# Drive.net
KiCad netlist of a schematic drawn in Altium Designer
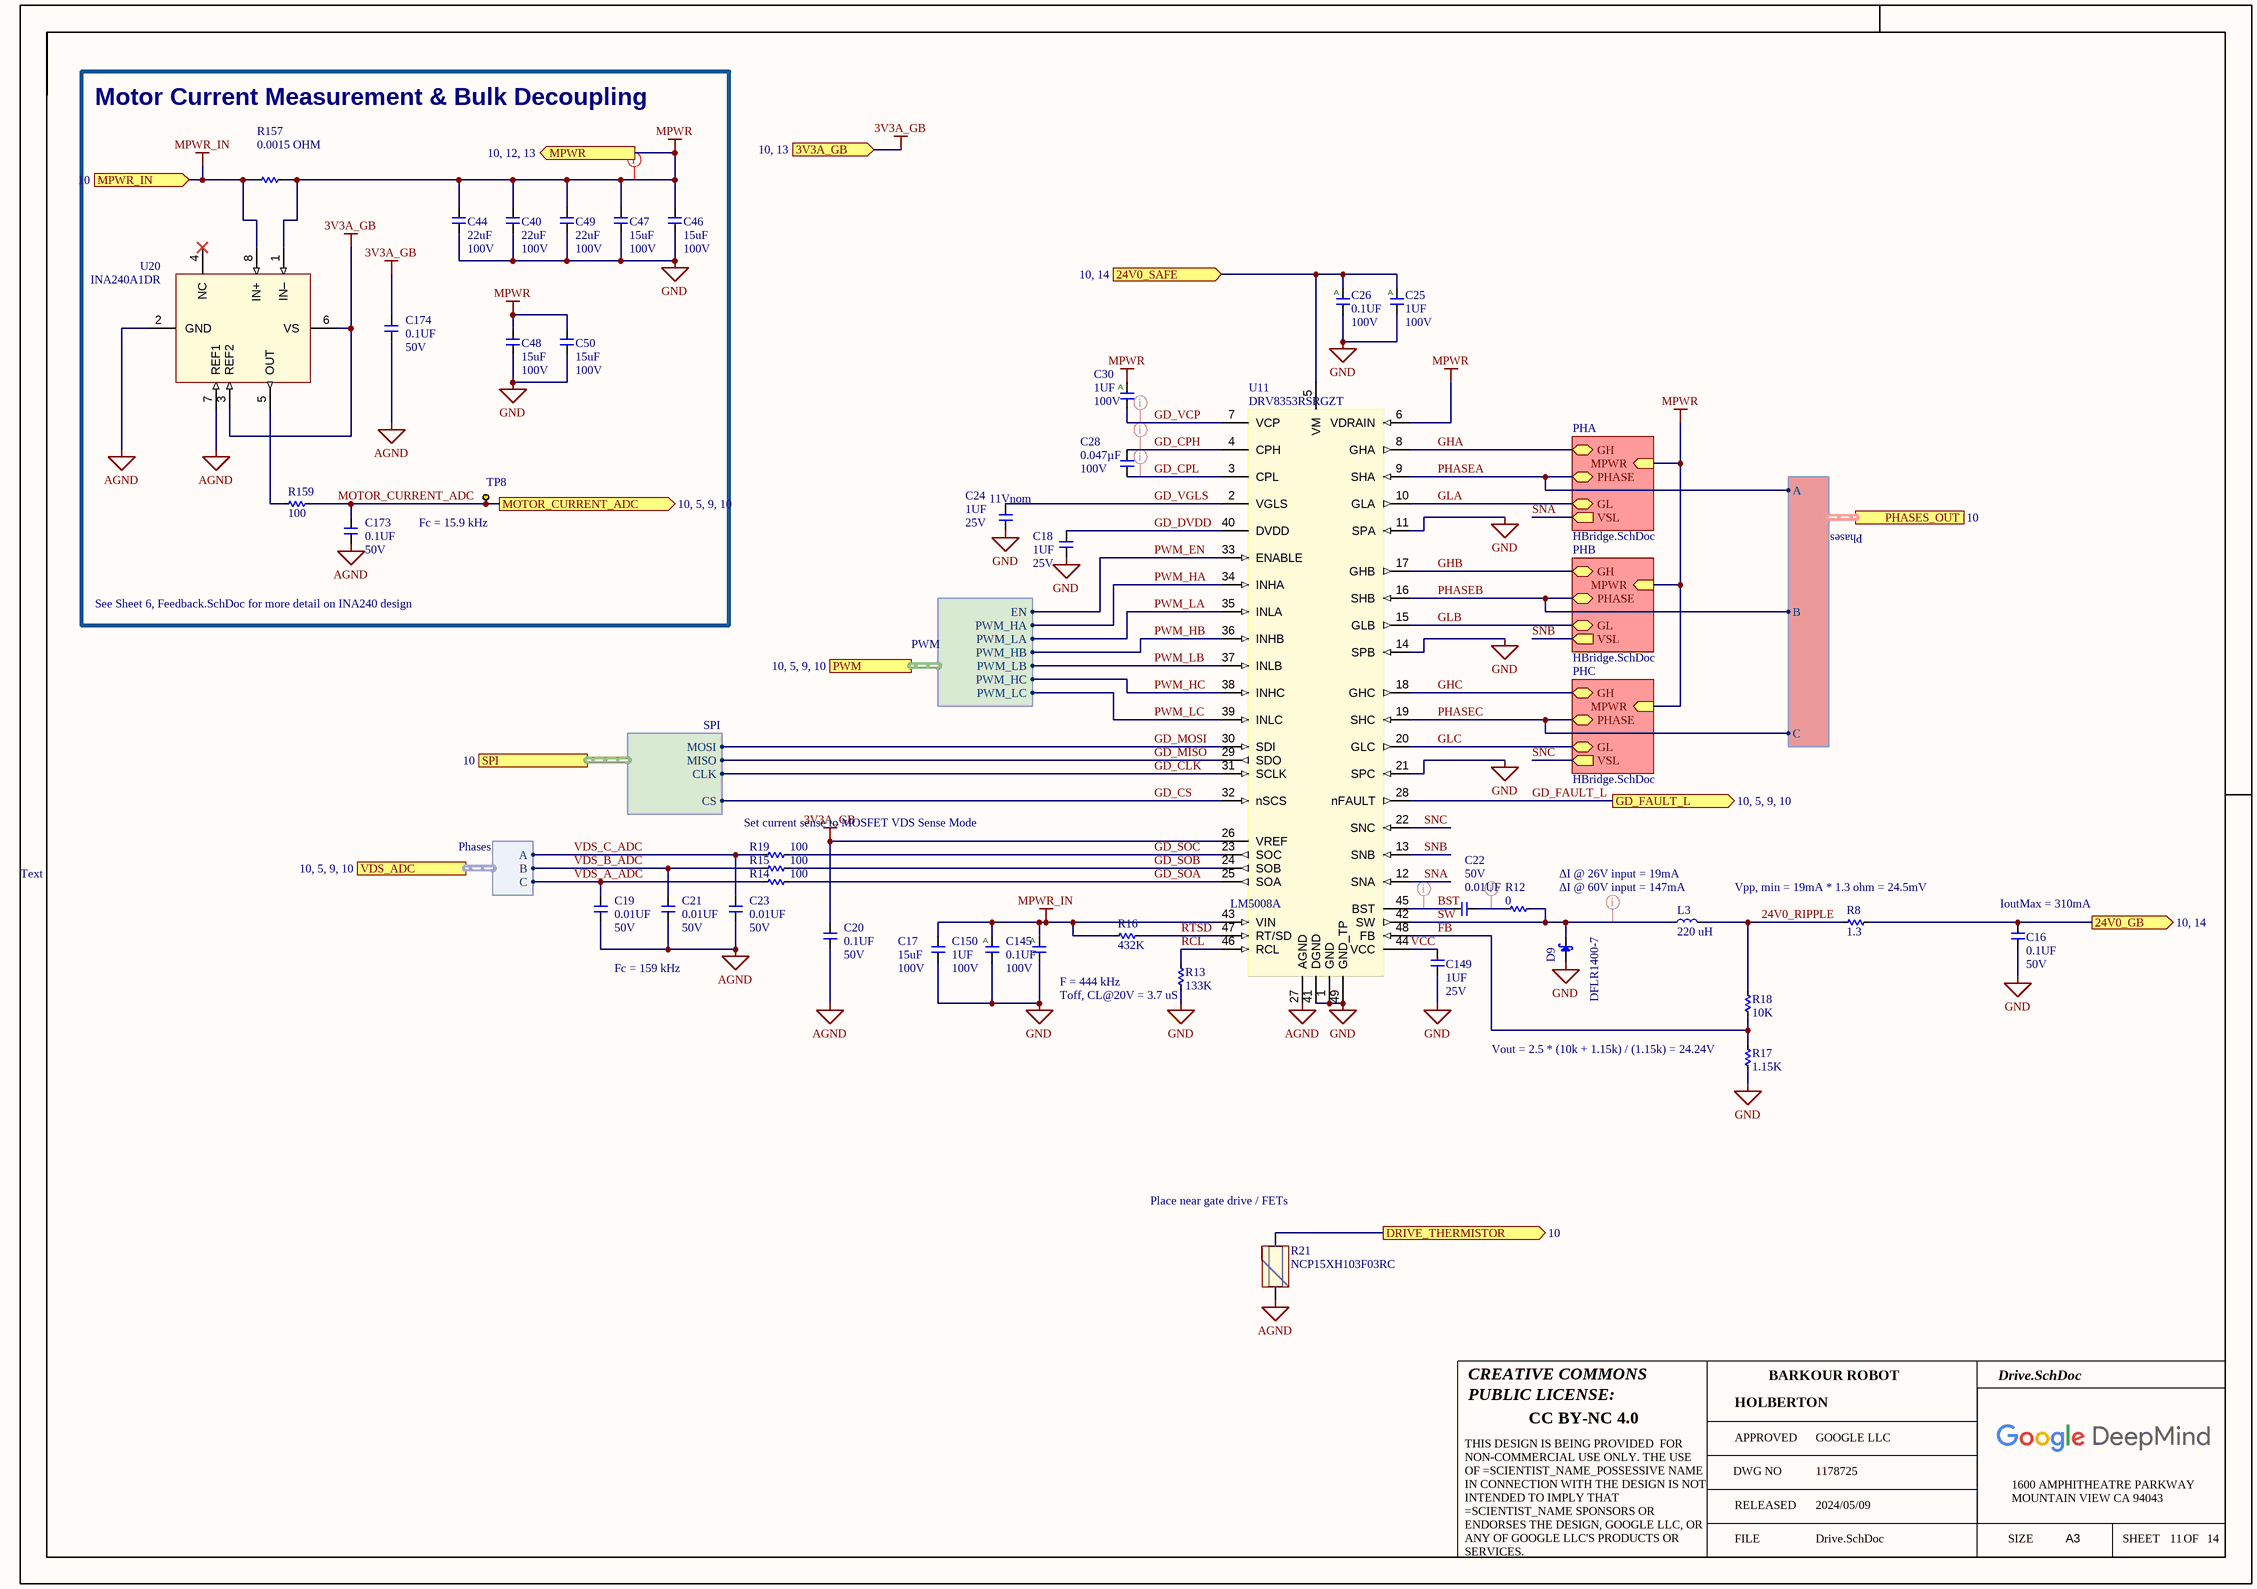
[diagram p0: Drive.SchDoc]

(export (version "E")
  (design (tool "Eeschema 10.0.6"))
  (components
    (comp (ref "C16")
      (value "0.1UF")
      (footprint "C0402")
      (description "CAP, CER, X5R, 0.1uF, 10%, 50V, 0402, 0.55mm")
      (fields
        (field (name "MFG") "YAGEO")
        (field (name "VOLTAGE") "50V")
        (field (name "Comment") "__Template_Cap")
      )
      (libsource (lib "AltiumReleaseLibDB") (part "__Template_Cap"))
    )
    (comp (ref "C17")
      (value "15uF")
      (footprint "C2220")
      (description "CAP, CER, X7S, 15uF, 100V, 20%, 2220, 2.8mm T")
      (fields
        (field (name "MFG") "TDK")
        (field (name "VOLTAGE") "100V")
        (field (name "Comment") "__Template_Cap")
      )
      (libsource (lib "AltiumReleaseLibDB") (part "__Template_Cap"))
    )
    (comp (ref "C18")
      (value "1UF")
      (footprint "C0402")
      (description "CAP, CER, X5R, 1uF, 10%, 25V, 0402")
      (fields
        (field (name "MFG") "TDK")
        (field (name "VOLTAGE") "25V")
        (field (name "Comment") "__Template_Cap")
      )
      (libsource (lib "AltiumReleaseLibDB") (part "__Template_Cap"))
    )
    (comp (ref "C19")
      (value "0.01UF")
      (footprint "C0402")
      (description "CAP, CER, X7R, 0.01uF, 50V, 20%, 0402, 0.56mm T")
      (fields
        (field (name "MFG") "KEMET")
        (field (name "VOLTAGE") "50V")
        (field (name "Comment") "__Template_Cap")
      )
      (libsource (lib "AltiumReleaseLibDB") (part "__Template_Cap"))
    )
    (comp (ref "C20")
      (value "0.1UF")
      (footprint "C0402")
      (description "CAP, CER, X5R, 0.1uF, 10%, 50V, 0402, 0.55mm")
      (fields
        (field (name "MFG") "YAGEO")
        (field (name "VOLTAGE") "50V")
        (field (name "Comment") "__Template_Cap")
      )
      (libsource (lib "AltiumReleaseLibDB") (part "__Template_Cap"))
    )
    (comp (ref "C21")
      (value "0.01UF")
      (footprint "C0402")
      (description "CAP, CER, X7R, 0.01uF, 50V, 20%, 0402, 0.56mm T")
      (fields
        (field (name "MFG") "KEMET")
        (field (name "VOLTAGE") "50V")
        (field (name "Comment") "__Template_Cap")
      )
      (libsource (lib "AltiumReleaseLibDB") (part "__Template_Cap"))
    )
    (comp (ref "C22")
      (value "0.01UF")
      (footprint "C0402")
      (description "CAP, CER, X7R, 0.01uF, 50V, 20%, 0402, 0.56mm T")
      (fields
        (field (name "MFG") "KEMET")
        (field (name "VOLTAGE") "50V")
        (field (name "Comment") "__Template_Cap")
      )
      (libsource (lib "AltiumReleaseLibDB") (part "__Template_Cap"))
    )
    (comp (ref "C23")
      (value "0.01UF")
      (footprint "C0402")
      (description "CAP, CER, X7R, 0.01uF, 50V, 20%, 0402, 0.56mm T")
      (fields
        (field (name "MFG") "KEMET")
        (field (name "VOLTAGE") "50V")
        (field (name "Comment") "__Template_Cap")
      )
      (libsource (lib "AltiumReleaseLibDB") (part "__Template_Cap"))
    )
    (comp (ref "C24")
      (value "1UF")
      (footprint "C0402")
      (description "CAP, CER, X5R, 1uF, 10%, 25V, 0402")
      (fields
        (field (name "MFG") "TDK")
        (field (name "VOLTAGE") "25V")
        (field (name "Comment") "__Template_Cap")
      )
      (libsource (lib "AltiumReleaseLibDB") (part "__Template_Cap"))
    )
    (comp (ref "C25")
      (value "1UF")
      (footprint "C0805")
      (description "CAP, CER, X7S, 1uF, 20%, 100V, 0805")
      (fields
        (field (name "MFG") "TDK")
        (field (name "VOLTAGE") "100V")
        (field (name "Comment") "__Template_Cap_Auto")
      )
      (libsource (lib "AltiumReleaseLibDB") (part "__Template_Cap_Auto"))
    )
    (comp (ref "C26")
      (value "0.1UF")
      (footprint "C0603")
      (description "CAP, CER, X7S, 0.1uF, 100V, 10%, 0603, AUTOGRADE")
      (fields
        (field (name "MFG") "TDK")
        (field (name "VOLTAGE") "100V")
        (field (name "Comment") "__Template_Cap_Auto")
      )
      (libsource (lib "AltiumReleaseLibDB") (part "__Template_Cap_Auto"))
    )
    (comp (ref "C28")
      (value "0.047µF")
      (footprint "C0603")
      (description "CAP, CER, X7R, 0.047uF, 100V, 10%, 0603, AUTOGRADE")
      (fields
        (field (name "MFG") "Samsung Electro-Mechanics")
        (field (name "VOLTAGE") "100V")
        (field (name "Comment") "__Template_Cap")
      )
      (libsource (lib "AltiumReleaseLibDB") (part "__Template_Cap"))
    )
    (comp (ref "C30")
      (value "1UF")
      (footprint "C0805")
      (description "CAP, CER, X7S, 1uF, 20%, 100V, 0805")
      (fields
        (field (name "MFG") "TDK")
        (field (name "VOLTAGE") "100V")
        (field (name "Comment") "__Template_Cap_Auto")
      )
      (libsource (lib "AltiumReleaseLibDB") (part "__Template_Cap_Auto"))
    )
    (comp (ref "C40")
      (value "22uF")
      (footprint "CAP_CKG57NX7S2A226M500JJ")
      (description "CAP CER 22UF 100V X7S SMD (6.00mm x 5.00mm x 5.5mm)")
      (fields
        (field (name "MFG") "TDK")
        (field (name "VOLTAGE") "100V")
        (field (name "Comment") "__Template_Cap")
      )
      (libsource (lib "AltiumReleaseLibDB") (part "__Template_Cap"))
    )
    (comp (ref "C44")
      (value "22uF")
      (footprint "CAP_CKG57NX7S2A226M500JJ")
      (description "CAP CER 22UF 100V X7S SMD (6.00mm x 5.00mm x 5.5mm)")
      (fields
        (field (name "MFG") "TDK")
        (field (name "VOLTAGE") "100V")
        (field (name "Comment") "__Template_Cap")
      )
      (libsource (lib "AltiumReleaseLibDB") (part "__Template_Cap"))
    )
    (comp (ref "C46")
      (value "15uF")
      (footprint "C2220")
      (description "CAP, CER, X7S, 15uF, 100V, 20%, 2220, 2.8mm T")
      (fields
        (field (name "MFG") "TDK")
        (field (name "VOLTAGE") "100V")
        (field (name "Comment") "__Template_Cap")
      )
      (libsource (lib "AltiumReleaseLibDB") (part "__Template_Cap"))
    )
    (comp (ref "C47")
      (value "15uF")
      (footprint "C2220")
      (description "CAP, CER, X7S, 15uF, 100V, 20%, 2220, 2.8mm T")
      (fields
        (field (name "MFG") "TDK")
        (field (name "VOLTAGE") "100V")
        (field (name "Comment") "__Template_Cap")
      )
      (libsource (lib "AltiumReleaseLibDB") (part "__Template_Cap"))
    )
    (comp (ref "C48")
      (value "15uF")
      (footprint "C2220")
      (description "CAP, CER, X7S, 15uF, 100V, 20%, 2220, 2.8mm T")
      (fields
        (field (name "MFG") "TDK")
        (field (name "VOLTAGE") "100V")
        (field (name "Comment") "__Template_Cap")
      )
      (libsource (lib "AltiumReleaseLibDB") (part "__Template_Cap"))
    )
    (comp (ref "C49")
      (value "22uF")
      (footprint "CAP_CKG57NX7S2A226M500JJ")
      (description "CAP CER 22UF 100V X7S SMD (6.00mm x 5.00mm x 5.5mm)")
      (fields
        (field (name "MFG") "TDK")
        (field (name "VOLTAGE") "100V")
        (field (name "Comment") "__Template_Cap")
      )
      (libsource (lib "AltiumReleaseLibDB") (part "__Template_Cap"))
    )
    (comp (ref "C50")
      (value "15uF")
      (footprint "C2220")
      (description "CAP, CER, X7S, 15uF, 100V, 20%, 2220, 2.8mm T")
      (fields
        (field (name "MFG") "TDK")
        (field (name "VOLTAGE") "100V")
        (field (name "Comment") "__Template_Cap")
      )
      (libsource (lib "AltiumReleaseLibDB") (part "__Template_Cap"))
    )
    (comp (ref "C145")
      (value "0.1UF")
      (footprint "C0603")
      (description "CAP, CER, X7S, 0.1uF, 100V, 10%, 0603, AUTOGRADE")
      (fields
        (field (name "MFG") "TDK")
        (field (name "VOLTAGE") "100V")
        (field (name "Comment") "__Template_Cap_Auto")
      )
      (libsource (lib "AltiumReleaseLibDB") (part "__Template_Cap_Auto"))
    )
    (comp (ref "C149")
      (value "1UF")
      (footprint "C0402")
      (description "CAP, CER, X5R, 1uF, 10%, 25V, 0402")
      (fields
        (field (name "MFG") "TDK")
        (field (name "VOLTAGE") "25V")
        (field (name "Comment") "__Template_Cap")
      )
      (libsource (lib "AltiumReleaseLibDB") (part "__Template_Cap"))
    )
    (comp (ref "C150")
      (value "1UF")
      (footprint "C0805")
      (description "CAP, CER, X7S, 1uF, 20%, 100V, 0805")
      (fields
        (field (name "MFG") "TDK")
        (field (name "VOLTAGE") "100V")
        (field (name "Comment") "__Template_Cap_Auto")
      )
      (libsource (lib "AltiumReleaseLibDB") (part "__Template_Cap_Auto"))
    )
    (comp (ref "C173")
      (value "0.1UF")
      (footprint "C0402")
      (description "CAP, CER, X5R, 0.1uF, 10%, 50V, 0402, 0.55mm")
      (fields
        (field (name "MFG") "YAGEO")
        (field (name "VOLTAGE") "50V")
        (field (name "Comment") "__Template_Cap")
      )
      (libsource (lib "AltiumReleaseLibDB") (part "__Template_Cap"))
    )
    (comp (ref "C174")
      (value "0.1UF")
      (footprint "C0402")
      (description "CAP, CER, X5R, 0.1uF, 10%, 50V, 0402, 0.55mm")
      (fields
        (field (name "MFG") "YAGEO")
        (field (name "VOLTAGE") "50V")
        (field (name "Comment") "__Template_Cap")
      )
      (libsource (lib "AltiumReleaseLibDB") (part "__Template_Cap"))
    )
    (comp (ref "D9")
      (value "DFLR1400-7")
      (footprint "POWERDI123_DFLS1100-7")
      (description "DIODE, SCHOTTKY, 100V, 1A, POWERDI123")
      (fields
        (field (name "MFG") "Diodes Incorporated")
        (field (name "Comment") "__Template_Diode_Schottky_A/K")
      )
      (libsource (lib "AltiumReleaseLibDB") (part "__Template_Diode_Schottky_A/K"))
    )
    (comp (ref "L3")
      (value "220 uH")
      (footprint "IND_74404054221")
      (description "220 µH Semi-Shielded Drum Core, Wirewound Inductor 500 mA 1.4Ohm Nonstandard")
      (fields (field (name "MFG") "Würth Elektronik") (field (name "Comment") "__Template_Inductor"))
      (libsource (lib "AltiumReleaseLibDB") (part "__Template_Inductor"))
    )
    (comp (ref "R8")
      (value "1.3")
      (footprint "R0805")
      (description "RES, 1.3, 1%, 1/2W, AUTOGRADE, 0805")
      (fields (field (name "MFG") "Panasonic Electronic Components"))
      (libsource (lib "AltiumReleaseLibDB") (part "__Template_Resistor"))
    )
    (comp (ref "R12")
      (value "0")
      (footprint "R0402")
      (description "RES, 0, JUMPER, 1/16W, 0402")
      (fields (field (name "MFG") "YAGEO"))
      (libsource (lib "AltiumReleaseLibDB") (part "__Template_Resistor"))
    )
    (comp (ref "R13")
      (value "133K")
      (footprint "R0402")
      (description "RES, 133K, 1%, 1/16W, 0402, AUTOGRADE")
      (fields (field (name "MFG") "VISHAY"))
      (libsource (lib "AltiumReleaseLibDB") (part "__Template_Resistor"))
    )
    (comp (ref "R14")
      (value "100")
      (footprint "R0402")
      (description "RES, 100, 1%, 1/10W, 0402, AUTO GRADE")
      (fields (field (name "MFG") "PANASONIC"))
      (libsource (lib "AltiumReleaseLibDB") (part "__Template_Resistor"))
    )
    (comp (ref "R15")
      (value "100")
      (footprint "R0402")
      (description "RES, 100, 1%, 1/10W, 0402, AUTO GRADE")
      (fields (field (name "MFG") "PANASONIC"))
      (libsource (lib "AltiumReleaseLibDB") (part "__Template_Resistor"))
    )
    (comp (ref "R16")
      (value "432K")
      (footprint "R0402")
      (description "RES, 432K, 1%, 1/16W, 0402")
      (fields (field (name "MFG") "VISHAY"))
      (libsource (lib "AltiumReleaseLibDB") (part "__Template_Resistor"))
    )
    (comp (ref "R17")
      (value "1.15K")
      (footprint "R0402")
      (description "RES, 1.15K, 1%, 1/16W, 0402")
      (fields (field (name "MFG") "VISHAY"))
      (libsource (lib "AltiumReleaseLibDB") (part "__Template_Resistor"))
    )
    (comp (ref "R18")
      (value "10K")
      (footprint "R0402")
      (description "RES, 10K, 1%, 1/10W, 0402, AUTOGRADE")
      (fields (field (name "MFG") "PANASONIC"))
      (libsource (lib "AltiumReleaseLibDB") (part "__Template_Resistor"))
    )
    (comp (ref "R19")
      (value "100")
      (footprint "R0402")
      (description "RES, 100, 1%, 1/10W, 0402, AUTO GRADE")
      (fields (field (name "MFG") "PANASONIC"))
      (libsource (lib "AltiumReleaseLibDB") (part "__Template_Resistor"))
    )
    (comp (ref "R21")
      (value "__Template_Thermistor")
      (footprint "R0402")
      (description "SENSOR, THERMISTOR, NTC, 10K, 1%, 3380K, 100mW, 0402")
      (fields (field (name "MFG") "Murata Electronics") (field (name "MFG P/N") "NCP15XH103F03RC"))
      (libsource (lib "AltiumReleaseLibDB") (part "__Template_Thermistor"))
    )
    (comp (ref "R157")
      (value "0.0015 OHM")
      (footprint "R2512")
      (description "RES, 0.0015, 1%, 3W, 2512")
      (fields (field (name "MFG") "TE Connectivity Passive Product"))
      (libsource (lib "AltiumReleaseLibDB") (part "__Template_Resistor"))
    )
    (comp (ref "R159")
      (value "100")
      (footprint "R0402")
      (description "RES, 100, 1%, 1/10W, 0402, AUTO GRADE")
      (fields (field (name "MFG") "PANASONIC"))
      (libsource (lib "AltiumReleaseLibDB") (part "__Template_Resistor"))
    )
    (comp (ref "TP8")
      (value "TEST_KEYSTONE5015")
      (footprint "TP_KEYSTONE_5015")
      (description "PC TEST POINT MINIATURE SMT")
      (fields (field (name "MFG") "Keystone Electronics"))
      (libsource (lib "miscellaneous") (part "TEST_KEYSTONE5015"))
    )
    (comp (ref "U11")
      (value "MOTOR_DRIVE_DRV8353RSRGZT")
      (footprint "VQFN50P700X700X100-48-TP_TP-CUST_NO_VIAS")
      (description "IC, MOTOR DRIVER, DRV8353, MULTIPHASE, BLDC, HALF BRIDGE, POWER MOSFET, 6V TO 95V VIN, VQFN-48")
      (fields (field (name "MFG") "Texas Instruments") (field (name "MFG P/N") "DRV8353RSRGZT"))
      (libsource (lib "AltiumReleaseLibDB") (part "MOTOR_DRIVE_DRV8353RSRGZT"))
    )
    (comp (ref "U20")
      (value "INA240A1DR")
      (footprint "TI SOIC-8 D0008A")
      (fields (field (name "MFG") "Texas Instruments"))
      (libsource (lib "MiscSch1") (part "INA240A1"))
    )
  )
  (nets
    (net (code "4") (name "/24V0_GB") (class "Default")
      (node (ref "C16") (pin "1") (pintype "passive"))
      (node (ref "R8") (pin "2") (pintype "passive"))
    )
    (net (code "5") (name "/24V0_RIPPLE") (class "Default")
      (node (ref "L3") (pin "2") (pintype "passive"))
      (node (ref "R18") (pin "2") (pintype "passive"))
      (node (ref "R8") (pin "1") (pintype "passive"))
    )
    (net (code "6") (name "/24V0_SAFE") (class "Default")
      (node (ref "C25") (pin "1") (pintype "passive"))
      (node (ref "C26") (pin "1") (pintype "passive"))
      (node (ref "U11") (pin "5") (pinfunction "VM_5") (pintype "power_in"))
    )
    (net (code "7") (name "/BST") (class "Default")
      (node (ref "C22") (pin "1") (pintype "passive"))
      (node (ref "U11") (pin "45") (pinfunction "BST_45") (pintype "power_in"))
    )
    (net (code "8") (name "/DRIVE_THERMISTOR") (class "Default")
      (node (ref "R21") (pin "1") (pintype "passive"))
    )
    (net (code "9") (name "/FB") (class "Default")
      (node (ref "R17") (pin "2") (pintype "passive"))
      (node (ref "R18") (pin "1") (pintype "passive"))
      (node (ref "U11") (pin "48") (pinfunction "FB_48") (pintype "input"))
    )
    (net (code "10") (name "/GD_CLK") (class "Default")
      (node (ref "U11") (pin "31") (pinfunction "SCLK_31") (pintype "input"))
    )
    (net (code "11") (name "/GD_CPH") (class "Default")
      (node (ref "C28") (pin "1") (pintype "passive"))
      (node (ref "U11") (pin "4") (pinfunction "CPH_4") (pintype "power_in"))
    )
    (net (code "12") (name "/GD_CPL") (class "Default")
      (node (ref "C28") (pin "2") (pintype "passive"))
      (node (ref "U11") (pin "3") (pinfunction "CPL_3") (pintype "power_in"))
    )
    (net (code "13") (name "/GD_CS") (class "Default")
      (node (ref "U11") (pin "32") (pinfunction "nSCS_32") (pintype "input"))
    )
    (net (code "14") (name "/GD_DVDD") (class "Default")
      (node (ref "C18") (pin "1") (pintype "passive"))
      (node (ref "U11") (pin "40") (pinfunction "DVDD_40") (pintype "power_in"))
    )
    (net (code "15") (name "/GD_FAULT_L") (class "Default")
      (node (ref "U11") (pin "28") (pinfunction "nFAULT_28") (pintype "output"))
    )
    (net (code "16") (name "/GD_MISO") (class "Default")
      (node (ref "U11") (pin "29") (pinfunction "SDO_29") (pintype "output"))
    )
    (net (code "17") (name "/GD_MOSI") (class "Default")
      (node (ref "U11") (pin "30") (pinfunction "SDI_30") (pintype "input"))
    )
    (net (code "18") (name "/GD_SOA") (class "Default")
      (node (ref "R14") (pin "2") (pintype "passive"))
      (node (ref "U11") (pin "25") (pinfunction "SOA_25") (pintype "output"))
    )
    (net (code "19") (name "/GD_SOB") (class "Default")
      (node (ref "R15") (pin "2") (pintype "passive"))
      (node (ref "U11") (pin "24") (pinfunction "SOB_24") (pintype "output"))
    )
    (net (code "20") (name "/GD_SOC") (class "Default")
      (node (ref "R19") (pin "2") (pintype "passive"))
      (node (ref "U11") (pin "23") (pinfunction "SOC_23") (pintype "output"))
    )
    (net (code "21") (name "/GD_VCP") (class "Default")
      (node (ref "C30") (pin "2") (pintype "passive"))
      (node (ref "U11") (pin "7") (pinfunction "VCP_7") (pintype "power_in"))
    )
    (net (code "22") (name "/GD_VGLS") (class "Default")
      (node (ref "C24") (pin "1") (pintype "passive"))
      (node (ref "U11") (pin "2") (pinfunction "VGLS_2") (pintype "power_in"))
    )
    (net (code "23") (name "/GHA") (class "Default")
      (node (ref "U11") (pin "8") (pinfunction "GHA_8") (pintype "output"))
    )
    (net (code "24") (name "/GHB") (class "Default")
      (node (ref "U11") (pin "17") (pinfunction "GHB_17") (pintype "output"))
    )
    (net (code "25") (name "/GHC") (class "Default")
      (node (ref "U11") (pin "18") (pinfunction "GHC_18") (pintype "output"))
    )
    (net (code "26") (name "/GLA") (class "Default")
      (node (ref "U11") (pin "10") (pinfunction "GLA_10") (pintype "output"))
    )
    (net (code "27") (name "/GLB") (class "Default")
      (node (ref "U11") (pin "15") (pinfunction "GLB_15") (pintype "output"))
    )
    (net (code "28") (name "/GLC") (class "Default")
      (node (ref "U11") (pin "20") (pinfunction "GLC_20") (pintype "output"))
    )
    (net (code "29") (name "/MOTOR_CURRENT_ADC") (class "Default")
      (node (ref "C173") (pin "1") (pintype "passive"))
      (node (ref "R159") (pin "2") (pintype "passive"))
      (node (ref "TP8") (pin "1") (pintype "passive"))
    )
    (net (code "30") (name "/PHASEA") (class "Default")
      (node (ref "U11") (pin "9") (pinfunction "SHA_9") (pintype "input"))
    )
    (net (code "31") (name "/PHASEB") (class "Default")
      (node (ref "U11") (pin "16") (pinfunction "SHB_16") (pintype "input"))
    )
    (net (code "32") (name "/PHASEC") (class "Default")
      (node (ref "U11") (pin "19") (pinfunction "SHC_19") (pintype "input"))
    )
    (net (code "33") (name "/PWM_EN") (class "Default")
      (node (ref "U11") (pin "33") (pinfunction "ENABLE_33") (pintype "input"))
    )
    (net (code "34") (name "/PWM_HA") (class "Default")
      (node (ref "U11") (pin "34") (pinfunction "INHA_34") (pintype "input"))
    )
    (net (code "35") (name "/PWM_HB") (class "Default")
      (node (ref "U11") (pin "36") (pinfunction "INHB_36") (pintype "input"))
    )
    (net (code "36") (name "/PWM_HC") (class "Default")
      (node (ref "U11") (pin "38") (pinfunction "INHC_38") (pintype "input"))
    )
    (net (code "37") (name "/PWM_LA") (class "Default")
      (node (ref "U11") (pin "35") (pinfunction "INLA_35") (pintype "input"))
    )
    (net (code "38") (name "/PWM_LB") (class "Default")
      (node (ref "U11") (pin "37") (pinfunction "INLB_37") (pintype "input"))
    )
    (net (code "39") (name "/PWM_LC") (class "Default")
      (node (ref "U11") (pin "39") (pinfunction "INLC_39") (pintype "input"))
    )
    (net (code "40") (name "/RCL") (class "Default")
      (node (ref "R13") (pin "2") (pintype "passive"))
      (node (ref "U11") (pin "46") (pinfunction "RCL_46") (pintype "input"))
    )
    (net (code "41") (name "/RTSD") (class "Default")
      (node (ref "R16") (pin "2") (pintype "passive"))
      (node (ref "U11") (pin "47") (pinfunction "RT/SD_47") (pintype "input"))
    )
    (net (code "42") (name "/SNA") (class "Default")
      (node (ref "U11") (pin "12") (pinfunction "SNA_12") (pintype "input"))
    )
    (net (code "43") (name "/SNB") (class "Default")
      (node (ref "U11") (pin "13") (pinfunction "SNB_13") (pintype "input"))
    )
    (net (code "44") (name "/SNC") (class "Default")
      (node (ref "U11") (pin "22") (pinfunction "SNC_22") (pintype "input"))
    )
    (net (code "45") (name "/SW") (class "Default")
      (node (ref "D9") (pin "K") (pintype "passive"))
      (node (ref "L3") (pin "1") (pintype "passive"))
      (node (ref "R12") (pin "2") (pintype "passive"))
      (node (ref "U11") (pin "42") (pinfunction "SW_42") (pintype "output"))
    )
    (net (code "46") (name "/VCC") (class "Default")
      (node (ref "C149") (pin "1") (pintype "passive"))
      (node (ref "U11") (pin "44") (pinfunction "VCC_44") (pintype "power_in"))
    )
    (net (code "47") (name "/VDS_A_ADC") (class "Default")
      (node (ref "C19") (pin "1") (pintype "passive"))
      (node (ref "R14") (pin "1") (pintype "passive"))
    )
    (net (code "48") (name "/VDS_B_ADC") (class "Default")
      (node (ref "C21") (pin "1") (pintype "passive"))
      (node (ref "R15") (pin "1") (pintype "passive"))
    )
    (net (code "49") (name "/VDS_C_ADC") (class "Default")
      (node (ref "C23") (pin "1") (pintype "passive"))
      (node (ref "R19") (pin "1") (pintype "passive"))
    )
    (net (code "53") (name "3V3A_GB") (class "Default")
      (node (ref "C174") (pin "1") (pintype "passive"))
      (node (ref "C20") (pin "1") (pintype "passive"))
      (node (ref "U11") (pin "26") (pinfunction "VREF_26") (pintype "power_in"))
      (node (ref "U20") (pin "3") (pinfunction "REF2_3") (pintype "input"))
      (node (ref "U20") (pin "6") (pinfunction "VS_6") (pintype "power_in"))
    )
    (net (code "54") (name "AGND") (class "Default")
      (node (ref "C173") (pin "2") (pintype "passive"))
      (node (ref "C174") (pin "2") (pintype "passive"))
      (node (ref "C19") (pin "2") (pintype "passive"))
      (node (ref "C20") (pin "2") (pintype "passive"))
      (node (ref "C21") (pin "2") (pintype "passive"))
      (node (ref "C23") (pin "2") (pintype "passive"))
      (node (ref "R21") (pin "2") (pintype "passive"))
      (node (ref "U11") (pin "27") (pinfunction "AGND_27") (pintype "power_in"))
      (node (ref "U20") (pin "2") (pinfunction "GND_2") (pintype "power_in"))
      (node (ref "U20") (pin "7") (pinfunction "REF1_7") (pintype "input"))
    )
    (net (code "55") (name "GND") (class "Default")
      (node (ref "C145") (pin "2") (pintype "passive"))
      (node (ref "C149") (pin "2") (pintype "passive"))
      (node (ref "C150") (pin "2") (pintype "passive"))
      (node (ref "C16") (pin "2") (pintype "passive"))
      (node (ref "C17") (pin "2") (pintype "passive"))
      (node (ref "C18") (pin "2") (pintype "passive"))
      (node (ref "C24") (pin "2") (pintype "passive"))
      (node (ref "C25") (pin "2") (pintype "passive"))
      (node (ref "C26") (pin "2") (pintype "passive"))
      (node (ref "C40") (pin "2") (pintype "passive"))
      (node (ref "C44") (pin "2") (pintype "passive"))
      (node (ref "C46") (pin "2") (pintype "passive"))
      (node (ref "C47") (pin "2") (pintype "passive"))
      (node (ref "C48") (pin "2") (pintype "passive"))
      (node (ref "C49") (pin "2") (pintype "passive"))
      (node (ref "C50") (pin "2") (pintype "passive"))
      (node (ref "D9") (pin "A") (pintype "passive"))
      (node (ref "R13") (pin "1") (pintype "passive"))
      (node (ref "R17") (pin "1") (pintype "passive"))
      (node (ref "U11") (pin "1") (pinfunction "GND_1") (pintype "power_in"))
      (node (ref "U11") (pin "11") (pinfunction "SPA_11") (pintype "input"))
      (node (ref "U11") (pin "14") (pinfunction "SPB_14") (pintype "input"))
      (node (ref "U11") (pin "21") (pinfunction "SPC_21") (pintype "input"))
      (node (ref "U11") (pin "41") (pinfunction "DGND_41") (pintype "power_in"))
      (node (ref "U11") (pin "49") (pinfunction "GND_TP_49") (pintype "power_in"))
    )
    (net (code "56") (name "MPWR") (class "Default")
      (node (ref "C30") (pin "1") (pintype "passive"))
      (node (ref "C40") (pin "1") (pintype "passive"))
      (node (ref "C44") (pin "1") (pintype "passive"))
      (node (ref "C46") (pin "1") (pintype "passive"))
      (node (ref "C47") (pin "1") (pintype "passive"))
      (node (ref "C48") (pin "1") (pintype "passive"))
      (node (ref "C49") (pin "1") (pintype "passive"))
      (node (ref "C50") (pin "1") (pintype "passive"))
      (node (ref "R157") (pin "2") (pintype "passive"))
      (node (ref "U11") (pin "6") (pinfunction "VDRAIN_6") (pintype "input"))
      (node (ref "U20") (pin "1") (pinfunction "IN–_1") (pintype "input"))
    )
    (net (code "57") (name "MPWR_IN") (class "Default")
      (node (ref "C145") (pin "1") (pintype "passive"))
      (node (ref "C150") (pin "1") (pintype "passive"))
      (node (ref "C17") (pin "1") (pintype "passive"))
      (node (ref "R157") (pin "1") (pintype "passive"))
      (node (ref "R16") (pin "1") (pintype "passive"))
      (node (ref "U11") (pin "43") (pinfunction "VIN_43") (pintype "input"))
      (node (ref "U20") (pin "8") (pinfunction "IN+_8") (pintype "input"))
    )
    (net (code "58") (name "Net-(C22-Pad2)") (class "Default")
      (node (ref "C22") (pin "2") (pintype "passive"))
      (node (ref "R12") (pin "1") (pintype "passive"))
    )
    (net (code "59") (name "Net-(U20-OUT)") (class "Default")
      (node (ref "R159") (pin "1") (pintype "passive"))
      (node (ref "U20") (pin "5") (pinfunction "OUT_5") (pintype "output"))
    )
    (net (code "60") (name "unconnected-(U20-NC-Pad4)") (class "Default")
      (node (ref "U20") (pin "4") (pinfunction "NC_4") (pintype "passive+no_connect"))
    )
  )
)
